# ButterWorth_8th_order_Filter.net
KiCad netlist of a schematic drawn in Altium Designer
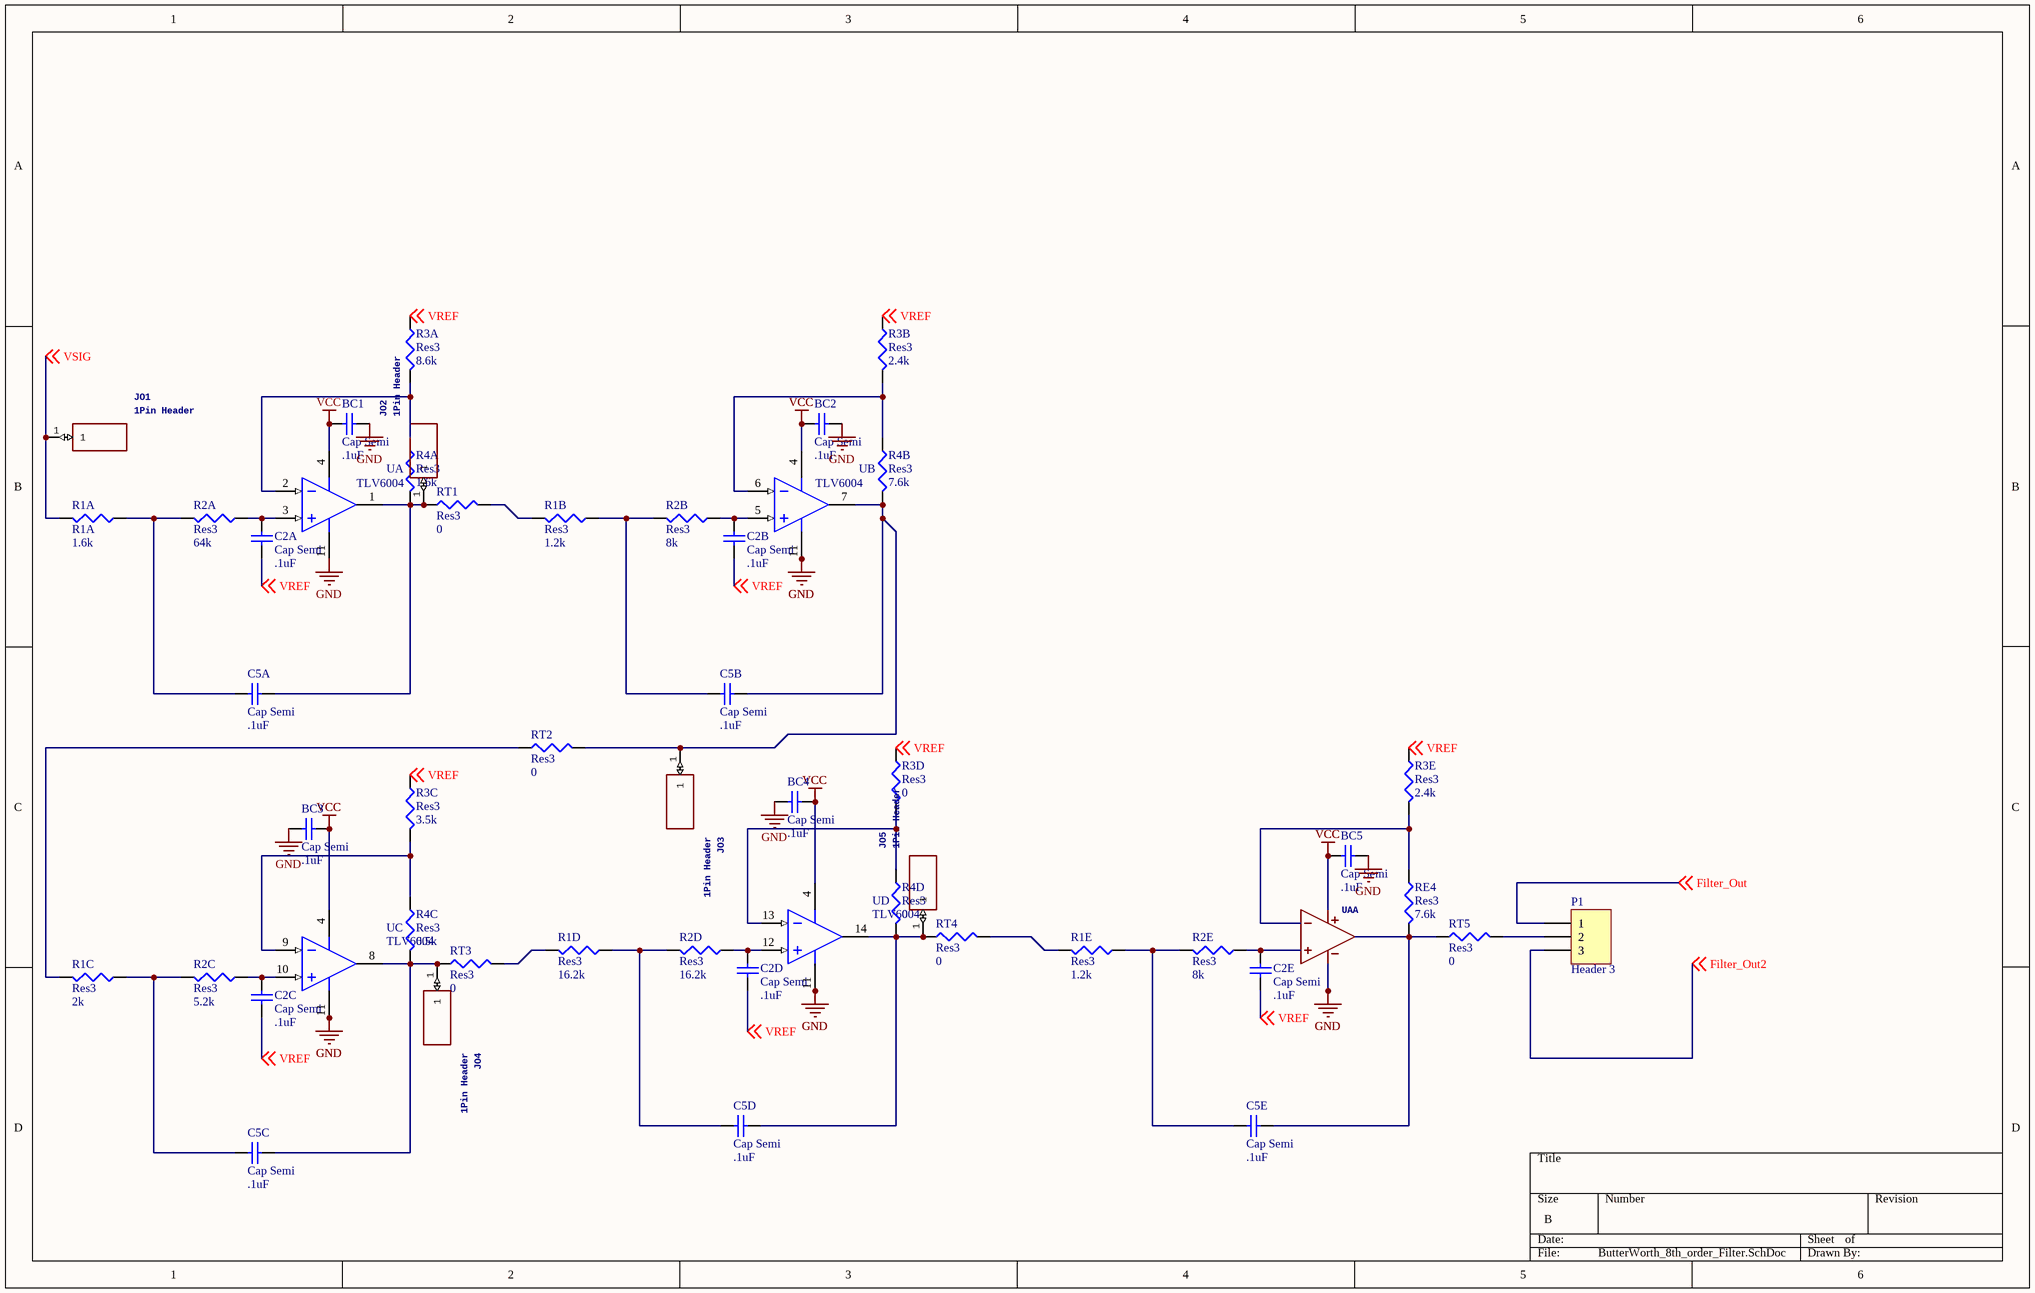
[diagram p0: ButterWorth_8th_order_Filter.SchDoc]

(export (version "E")
  (design (tool "Eeschema 10.0.6"))
  (components
    (comp (ref "BC1")
      (value "Cap Semi")
      (footprint "1608[0603]")
      (description "Capacitor (Semiconductor SIM Model)")
      (fields (field (name "ALTIUM_VALUE") ".1uF") (field (name "PUBLISHER") "Altium Limited"))
      (libsource (lib "Miscellaneous Devices") (part "Cap Semi"))
    )
    (comp (ref "BC2")
      (value "Cap Semi")
      (footprint "1608[0603]")
      (description "Capacitor (Semiconductor SIM Model)")
      (fields (field (name "ALTIUM_VALUE") ".1uF") (field (name "PUBLISHER") "Altium Limited"))
      (libsource (lib "Miscellaneous Devices") (part "Cap Semi"))
    )
    (comp (ref "BC3")
      (value "Cap Semi")
      (footprint "1608[0603]")
      (description "Capacitor (Semiconductor SIM Model)")
      (fields (field (name "ALTIUM_VALUE") ".1uF") (field (name "PUBLISHER") "Altium Limited"))
      (libsource (lib "Miscellaneous Devices") (part "Cap Semi"))
    )
    (comp (ref "BC4")
      (value "Cap Semi")
      (footprint "1608[0603]")
      (description "Capacitor (Semiconductor SIM Model)")
      (fields (field (name "ALTIUM_VALUE") ".1uF") (field (name "PUBLISHER") "Altium Limited"))
      (libsource (lib "Miscellaneous Devices") (part "Cap Semi"))
    )
    (comp (ref "BC5")
      (value "Cap Semi")
      (footprint "1608[0603]")
      (description "Capacitor (Semiconductor SIM Model)")
      (fields (field (name "ALTIUM_VALUE") ".1uF") (field (name "PUBLISHER") "Altium Limited"))
      (libsource (lib "Miscellaneous Devices") (part "Cap Semi"))
    )
    (comp (ref "C2A")
      (value "Cap Semi")
      (footprint "1608[0603]")
      (description "Capacitor (Semiconductor SIM Model)")
      (fields (field (name "ALTIUM_VALUE") ".1uF") (field (name "PUBLISHER") "Altium Limited"))
      (libsource (lib "Miscellaneous Devices") (part "Cap Semi"))
    )
    (comp (ref "C2B")
      (value "Cap Semi")
      (footprint "1608[0603]")
      (description "Capacitor (Semiconductor SIM Model)")
      (fields (field (name "ALTIUM_VALUE") ".1uF") (field (name "PUBLISHER") "Altium Limited"))
      (libsource (lib "Miscellaneous Devices") (part "Cap Semi"))
    )
    (comp (ref "C2C")
      (value "Cap Semi")
      (footprint "1608[0603]")
      (description "Capacitor (Semiconductor SIM Model)")
      (fields (field (name "ALTIUM_VALUE") ".1uF") (field (name "PUBLISHER") "Altium Limited"))
      (libsource (lib "Miscellaneous Devices") (part "Cap Semi"))
    )
    (comp (ref "C2D")
      (value "Cap Semi")
      (footprint "1608[0603]")
      (description "Capacitor (Semiconductor SIM Model)")
      (fields (field (name "ALTIUM_VALUE") ".1uF") (field (name "PUBLISHER") "Altium Limited"))
      (libsource (lib "Miscellaneous Devices") (part "Cap Semi"))
    )
    (comp (ref "C2E")
      (value "Cap Semi")
      (footprint "1608[0603]")
      (description "Capacitor (Semiconductor SIM Model)")
      (fields (field (name "ALTIUM_VALUE") ".1uF") (field (name "PUBLISHER") "Altium Limited"))
      (libsource (lib "Miscellaneous Devices") (part "Cap Semi"))
    )
    (comp (ref "C5A")
      (value "Cap Semi")
      (footprint "C1206")
      (description "Capacitor (Semiconductor SIM Model)")
      (fields (field (name "ALTIUM_VALUE") ".1uF") (field (name "PUBLISHER") "Altium Limited"))
      (libsource (lib "Miscellaneous Devices") (part "Cap Semi"))
    )
    (comp (ref "C5B")
      (value "Cap Semi")
      (footprint "C1206")
      (description "Capacitor (Semiconductor SIM Model)")
      (fields (field (name "ALTIUM_VALUE") ".1uF") (field (name "PUBLISHER") "Altium Limited"))
      (libsource (lib "Miscellaneous Devices") (part "Cap Semi"))
    )
    (comp (ref "C5C")
      (value "Cap Semi")
      (footprint "C1206")
      (description "Capacitor (Semiconductor SIM Model)")
      (fields (field (name "ALTIUM_VALUE") ".1uF") (field (name "PUBLISHER") "Altium Limited"))
      (libsource (lib "Miscellaneous Devices") (part "Cap Semi"))
    )
    (comp (ref "C5D")
      (value "Cap Semi")
      (footprint "C1206")
      (description "Capacitor (Semiconductor SIM Model)")
      (fields (field (name "ALTIUM_VALUE") ".1uF") (field (name "PUBLISHER") "Altium Limited"))
      (libsource (lib "Miscellaneous Devices") (part "Cap Semi"))
    )
    (comp (ref "C5E")
      (value "Cap Semi")
      (footprint "C1206")
      (description "Capacitor (Semiconductor SIM Model)")
      (fields (field (name "ALTIUM_VALUE") ".1uF") (field (name "PUBLISHER") "Altium Limited"))
      (libsource (lib "Miscellaneous Devices") (part "Cap Semi"))
    )
    (comp (ref "JO1")
      (value "1Pin Header")
      (footprint "68000-401HLF")
      (fields
        (field (name "MANUFACTURER_PART_NUMBER") "68000-401HLF")
        (field (name "RS_PART_NUMBER") "8632706")
      )
      (libsource (lib "68000-401HLF") (part "68000-401HLF"))
    )
    (comp (ref "JO2")
      (value "1Pin Header")
      (footprint "68000-401HLF")
      (fields
        (field (name "MANUFACTURER_PART_NUMBER") "68000-401HLF")
        (field (name "RS_PART_NUMBER") "8632706")
      )
      (libsource (lib "68000-401HLF") (part "68000-401HLF"))
    )
    (comp (ref "JO3")
      (value "1Pin Header")
      (footprint "68000-401HLF")
      (fields
        (field (name "MANUFACTURER_PART_NUMBER") "68000-401HLF")
        (field (name "RS_PART_NUMBER") "8632706")
      )
      (libsource (lib "68000-401HLF") (part "68000-401HLF"))
    )
    (comp (ref "JO4")
      (value "1Pin Header")
      (footprint "68000-401HLF")
      (fields
        (field (name "MANUFACTURER_PART_NUMBER") "68000-401HLF")
        (field (name "RS_PART_NUMBER") "8632706")
      )
      (libsource (lib "68000-401HLF") (part "68000-401HLF"))
    )
    (comp (ref "JO5")
      (value "1Pin Header")
      (footprint "68000-401HLF")
      (fields
        (field (name "MANUFACTURER_PART_NUMBER") "68000-401HLF")
        (field (name "RS_PART_NUMBER") "8632706")
      )
      (libsource (lib "68000-401HLF") (part "68000-401HLF"))
    )
    (comp (ref "P1")
      (value "Header 3")
      (footprint "HDRV3W95P0X254_1X3_762X254X869")
      (description "Header, 3-Pin")
      (fields (field (name "PUBLISHER") "Altium Limited"))
      (libsource (lib "Miscellaneous Connectors") (part "Header 3"))
    )
    (comp (ref "R1A")
      (value "R1A")
      (footprint "1608[0603]")
      (description "Resistor")
      (fields (field (name "ALTIUM_VALUE") "1.6k") (field (name "PUBLISHER") "Altium Limited"))
      (libsource (lib "Miscellaneous Devices") (part "Res3"))
    )
    (comp (ref "R1B")
      (value "Res3")
      (footprint "1608[0603]")
      (description "Resistor")
      (fields (field (name "ALTIUM_VALUE") "1.2k") (field (name "PUBLISHER") "Altium Limited"))
      (libsource (lib "Miscellaneous Devices") (part "Res3"))
    )
    (comp (ref "R1C")
      (value "Res3")
      (footprint "1608[0603]")
      (description "Resistor")
      (fields (field (name "ALTIUM_VALUE") "2k") (field (name "PUBLISHER") "Altium Limited"))
      (libsource (lib "Miscellaneous Devices") (part "Res3"))
    )
    (comp (ref "R1D")
      (value "Res3")
      (footprint "1608[0603]")
      (description "Resistor")
      (fields (field (name "ALTIUM_VALUE") "16.2k") (field (name "PUBLISHER") "Altium Limited"))
      (libsource (lib "Miscellaneous Devices") (part "Res3"))
    )
    (comp (ref "R1E")
      (value "Res3")
      (footprint "1608[0603]")
      (description "Resistor")
      (fields (field (name "ALTIUM_VALUE") "1.2k") (field (name "PUBLISHER") "Altium Limited"))
      (libsource (lib "Miscellaneous Devices") (part "Res3"))
    )
    (comp (ref "R2A")
      (value "Res3")
      (footprint "1608[0603]")
      (description "Resistor")
      (fields (field (name "ALTIUM_VALUE") "64k") (field (name "PUBLISHER") "Altium Limited"))
      (libsource (lib "Miscellaneous Devices") (part "Res3"))
    )
    (comp (ref "R2B")
      (value "Res3")
      (footprint "1608[0603]")
      (description "Resistor")
      (fields (field (name "ALTIUM_VALUE") "8k") (field (name "PUBLISHER") "Altium Limited"))
      (libsource (lib "Miscellaneous Devices") (part "Res3"))
    )
    (comp (ref "R2C")
      (value "Res3")
      (footprint "1608[0603]")
      (description "Resistor")
      (fields (field (name "ALTIUM_VALUE") "5.2k") (field (name "PUBLISHER") "Altium Limited"))
      (libsource (lib "Miscellaneous Devices") (part "Res3"))
    )
    (comp (ref "R2D")
      (value "Res3")
      (footprint "1608[0603]")
      (description "Resistor")
      (fields (field (name "ALTIUM_VALUE") "16.2k") (field (name "PUBLISHER") "Altium Limited"))
      (libsource (lib "Miscellaneous Devices") (part "Res3"))
    )
    (comp (ref "R2E")
      (value "Res3")
      (footprint "1608[0603]")
      (description "Resistor")
      (fields (field (name "ALTIUM_VALUE") "8k") (field (name "PUBLISHER") "Altium Limited"))
      (libsource (lib "Miscellaneous Devices") (part "Res3"))
    )
    (comp (ref "R3A")
      (value "Res3")
      (footprint "1608[0603]")
      (description "Resistor")
      (fields (field (name "ALTIUM_VALUE") "8.6k") (field (name "PUBLISHER") "Altium Limited"))
      (libsource (lib "Miscellaneous Devices") (part "Res3"))
    )
    (comp (ref "R3B")
      (value "Res3")
      (footprint "1608[0603]")
      (description "Resistor")
      (fields (field (name "ALTIUM_VALUE") "2.4k") (field (name "PUBLISHER") "Altium Limited"))
      (libsource (lib "Miscellaneous Devices") (part "Res3"))
    )
    (comp (ref "R3C")
      (value "Res3")
      (footprint "1608[0603]")
      (description "Resistor")
      (fields (field (name "ALTIUM_VALUE") "3.5k") (field (name "PUBLISHER") "Altium Limited"))
      (libsource (lib "Miscellaneous Devices") (part "Res3"))
    )
    (comp (ref "R3D")
      (value "Res3")
      (footprint "1608[0603]")
      (description "Resistor")
      (fields (field (name "ALTIUM_VALUE") "0") (field (name "PUBLISHER") "Altium Limited"))
      (libsource (lib "Miscellaneous Devices") (part "Res3"))
    )
    (comp (ref "R3E")
      (value "Res3")
      (footprint "1608[0603]")
      (description "Resistor")
      (fields (field (name "ALTIUM_VALUE") "2.4k") (field (name "PUBLISHER") "Altium Limited"))
      (libsource (lib "Miscellaneous Devices") (part "Res3"))
    )
    (comp (ref "R4A")
      (value "Res3")
      (footprint "1608[0603]")
      (description "Resistor")
      (fields (field (name "ALTIUM_VALUE") "1.6k") (field (name "PUBLISHER") "Altium Limited"))
      (libsource (lib "Miscellaneous Devices") (part "Res3"))
    )
    (comp (ref "R4B")
      (value "Res3")
      (footprint "1608[0603]")
      (description "Resistor")
      (fields (field (name "ALTIUM_VALUE") "7.6k") (field (name "PUBLISHER") "Altium Limited"))
      (libsource (lib "Miscellaneous Devices") (part "Res3"))
    )
    (comp (ref "R4C")
      (value "Res3")
      (footprint "1608[0603]")
      (description "Resistor")
      (fields (field (name "ALTIUM_VALUE") "6.5k") (field (name "PUBLISHER") "Altium Limited"))
      (libsource (lib "Miscellaneous Devices") (part "Res3"))
    )
    (comp (ref "R4D")
      (value "Res3")
      (footprint "1608[0603]")
      (description "Resistor")
      (fields (field (name "ALTIUM_VALUE") "0") (field (name "PUBLISHER") "Altium Limited"))
      (libsource (lib "Miscellaneous Devices") (part "Res3"))
    )
    (comp (ref "RE4")
      (value "Res3")
      (footprint "1608[0603]")
      (description "Resistor")
      (fields (field (name "ALTIUM_VALUE") "7.6k") (field (name "PUBLISHER") "Altium Limited"))
      (libsource (lib "Miscellaneous Devices") (part "Res3"))
    )
    (comp (ref "RT1")
      (value "Res3")
      (footprint "1608[0603]")
      (description "Resistor")
      (fields (field (name "ALTIUM_VALUE") "0") (field (name "PUBLISHER") "Altium Limited"))
      (libsource (lib "Miscellaneous Devices") (part "Res3"))
    )
    (comp (ref "RT2")
      (value "Res3")
      (footprint "1608[0603]")
      (description "Resistor")
      (fields (field (name "ALTIUM_VALUE") "0") (field (name "PUBLISHER") "Altium Limited"))
      (libsource (lib "Miscellaneous Devices") (part "Res3"))
    )
    (comp (ref "RT3")
      (value "Res3")
      (footprint "1608[0603]")
      (description "Resistor")
      (fields (field (name "ALTIUM_VALUE") "0") (field (name "PUBLISHER") "Altium Limited"))
      (libsource (lib "Miscellaneous Devices") (part "Res3"))
    )
    (comp (ref "RT4")
      (value "Res3")
      (footprint "1608[0603]")
      (description "Resistor")
      (fields (field (name "ALTIUM_VALUE") "0") (field (name "PUBLISHER") "Altium Limited"))
      (libsource (lib "Miscellaneous Devices") (part "Res3"))
    )
    (comp (ref "RT5")
      (value "Res3")
      (footprint "1608[0603]")
      (description "Resistor")
      (fields (field (name "ALTIUM_VALUE") "0") (field (name "PUBLISHER") "Altium Limited"))
      (libsource (lib "Miscellaneous Devices") (part "Res3"))
    )
    (comp (ref "U")
      (value "TLV6004")
      (footprint "SOP65P640X120-14N")
      (description "Low Power Quad Differential Comparator")
      (fields (field (name "PUBLISHER") "Altium Limited"))
      (libsource (lib "TI Analog Comparator") (part "LP2901D"))
    )
    (comp (ref "UAA")
      (value "Universal Opamp model that allows 4 different levels of simulation accuracy.  See ./examples/Educational/UniversalOpamp2.asc for details.  En and in are equivalent voltage and current noises.  Enk and ink are the respective corner frequencies.  Phimargin is used to set the 2nd pole or delay to the approximate phase margin for level.3a and level.3b.  This version uses the new, experimental level 2 switch as the output devices.")
      (footprint "SOT95P280X100-5N")
      (fields (field (name "LIBRARYNAME") "Opamps"))
      (libsource (lib "Opamps") (part "UNIVERSALOPAMP2"))
    )
  )
  (nets
    (net (code "1") (name "Filter_Out") (class "Default")
      (node (ref "P1") (pin "1") (pinfunction "1_1") (pintype "passive"))
    )
    (net (code "2") (name "Filter_Out2") (class "Default")
      (node (ref "P1") (pin "3") (pinfunction "3_3") (pintype "passive"))
    )
    (net (code "3") (name "GND") (class "Default")
      (node (ref "BC1") (pin "1") (pinfunction "1_1") (pintype "passive"))
      (node (ref "BC2") (pin "1") (pinfunction "1_1") (pintype "passive"))
      (node (ref "BC3") (pin "2") (pinfunction "2_2") (pintype "passive"))
      (node (ref "BC4") (pin "2") (pinfunction "2_2") (pintype "passive"))
      (node (ref "BC5") (pin "1") (pinfunction "1_1") (pintype "passive"))
      (node (ref "U") (pin "11") (pinfunction "V-_11") (pintype "power_in"))
      (node (ref "UAA") (pin "2") (pinfunction "V-_2") (pintype "power_in"))
    )
    (net (code "4") (name "Net-(C5A-Pad2)") (class "Default")
      (node (ref "C5A") (pin "2") (pinfunction "2_2") (pintype "passive"))
      (node (ref "R1A") (pin "2") (pinfunction "2_2") (pintype "passive"))
      (node (ref "R2A") (pin "1") (pinfunction "1_1") (pintype "passive"))
    )
    (net (code "5") (name "Net-(C5B-Pad2)") (class "Default")
      (node (ref "C5B") (pin "2") (pinfunction "2_2") (pintype "passive"))
      (node (ref "R1B") (pin "2") (pinfunction "2_2") (pintype "passive"))
      (node (ref "R2B") (pin "1") (pinfunction "1_1") (pintype "passive"))
    )
    (net (code "6") (name "Net-(C5C-Pad2)") (class "Default")
      (node (ref "C5C") (pin "2") (pinfunction "2_2") (pintype "passive"))
      (node (ref "R1C") (pin "2") (pinfunction "2_2") (pintype "passive"))
      (node (ref "R2C") (pin "1") (pinfunction "1_1") (pintype "passive"))
    )
    (net (code "7") (name "Net-(C5D-Pad2)") (class "Default")
      (node (ref "C5D") (pin "2") (pinfunction "2_2") (pintype "passive"))
      (node (ref "R1D") (pin "2") (pinfunction "2_2") (pintype "passive"))
      (node (ref "R2D") (pin "1") (pinfunction "1_1") (pintype "passive"))
    )
    (net (code "8") (name "Net-(C5E-Pad2)") (class "Default")
      (node (ref "C5E") (pin "2") (pinfunction "2_2") (pintype "passive"))
      (node (ref "R1E") (pin "2") (pinfunction "2_2") (pintype "passive"))
      (node (ref "R2E") (pin "1") (pinfunction "1_1") (pintype "passive"))
    )
    (net (code "9") (name "Net-(P1-Pad2)") (class "Default")
      (node (ref "P1") (pin "2") (pinfunction "2_2") (pintype "passive"))
      (node (ref "RT5") (pin "1") (pinfunction "1_1") (pintype "passive"))
    )
    (net (code "10") (name "Net-(R1B-Pad1)") (class "Default")
      (node (ref "R1B") (pin "1") (pinfunction "1_1") (pintype "passive"))
      (node (ref "RT1") (pin "1") (pinfunction "1_1") (pintype "passive"))
    )
    (net (code "11") (name "Net-(R1C-Pad1)") (class "Default")
      (node (ref "R1C") (pin "1") (pinfunction "1_1") (pintype "passive"))
      (node (ref "RT2") (pin "2") (pinfunction "2_2") (pintype "passive"))
    )
    (net (code "12") (name "Net-(R1D-Pad1)") (class "Default")
      (node (ref "R1D") (pin "1") (pinfunction "1_1") (pintype "passive"))
      (node (ref "RT3") (pin "1") (pinfunction "1_1") (pintype "passive"))
    )
    (net (code "13") (name "Net-(R1E-Pad1)") (class "Default")
      (node (ref "R1E") (pin "1") (pinfunction "1_1") (pintype "passive"))
      (node (ref "RT4") (pin "1") (pinfunction "1_1") (pintype "passive"))
    )
    (net (code "14") (name "Net-(UA-IN+)") (class "Default")
      (node (ref "C2A") (pin "2") (pinfunction "2_2") (pintype "passive"))
      (node (ref "R2A") (pin "2") (pinfunction "2_2") (pintype "passive"))
      (node (ref "U") (pin "3") (pinfunction "IN+_3") (pintype "input"))
    )
    (net (code "15") (name "Net-(UA-IN-)") (class "Default")
      (node (ref "R3A") (pin "1") (pinfunction "1_1") (pintype "passive"))
      (node (ref "R4A") (pin "2") (pinfunction "2_2") (pintype "passive"))
      (node (ref "U") (pin "2") (pinfunction "IN-_2") (pintype "input"))
    )
    (net (code "16") (name "Net-(UA-OUT)") (class "Default")
      (node (ref "C5A") (pin "1") (pinfunction "1_1") (pintype "passive"))
      (node (ref "JO2") (pin "1") (pinfunction "1_1") (pintype "bidirectional"))
      (node (ref "R4A") (pin "1") (pinfunction "1_1") (pintype "passive"))
      (node (ref "RT1") (pin "2") (pinfunction "2_2") (pintype "passive"))
      (node (ref "U") (pin "1") (pinfunction "OUT_1") (pintype "open_collector"))
    )
    (net (code "17") (name "Net-(UAA-IN+)") (class "Default")
      (node (ref "C2E") (pin "2") (pinfunction "2_2") (pintype "passive"))
      (node (ref "R2E") (pin "2") (pinfunction "2_2") (pintype "passive"))
      (node (ref "UAA") (pin "3") (pinfunction "IN+_3") (pintype "input"))
    )
    (net (code "18") (name "Net-(UAA-IN-)") (class "Default")
      (node (ref "R3E") (pin "1") (pinfunction "1_1") (pintype "passive"))
      (node (ref "RE4") (pin "2") (pinfunction "2_2") (pintype "passive"))
      (node (ref "UAA") (pin "4") (pinfunction "IN-_4") (pintype "input"))
    )
    (net (code "19") (name "Net-(UAA-OUT)") (class "Default")
      (node (ref "C5E") (pin "1") (pinfunction "1_1") (pintype "passive"))
      (node (ref "RE4") (pin "1") (pinfunction "1_1") (pintype "passive"))
      (node (ref "RT5") (pin "2") (pinfunction "2_2") (pintype "passive"))
      (node (ref "UAA") (pin "1") (pinfunction "OUT_1") (pintype "output"))
    )
    (net (code "20") (name "Net-(UB-IN+)") (class "Default")
      (node (ref "C2B") (pin "2") (pinfunction "2_2") (pintype "passive"))
      (node (ref "R2B") (pin "2") (pinfunction "2_2") (pintype "passive"))
      (node (ref "U") (pin "5") (pinfunction "IN+_5") (pintype "input"))
    )
    (net (code "21") (name "Net-(UB-IN-)") (class "Default")
      (node (ref "R3B") (pin "1") (pinfunction "1_1") (pintype "passive"))
      (node (ref "R4B") (pin "2") (pinfunction "2_2") (pintype "passive"))
      (node (ref "U") (pin "6") (pinfunction "IN-_6") (pintype "input"))
    )
    (net (code "22") (name "Net-(UB-OUT)") (class "Default")
      (node (ref "C5B") (pin "1") (pinfunction "1_1") (pintype "passive"))
      (node (ref "JO3") (pin "1") (pinfunction "1_1") (pintype "bidirectional"))
      (node (ref "R4B") (pin "1") (pinfunction "1_1") (pintype "passive"))
      (node (ref "RT2") (pin "1") (pinfunction "1_1") (pintype "passive"))
      (node (ref "U") (pin "7") (pinfunction "OUT_7") (pintype "open_collector"))
    )
    (net (code "23") (name "Net-(UC-IN+)") (class "Default")
      (node (ref "C2C") (pin "2") (pinfunction "2_2") (pintype "passive"))
      (node (ref "R2C") (pin "2") (pinfunction "2_2") (pintype "passive"))
      (node (ref "U") (pin "10") (pinfunction "IN+_10") (pintype "input"))
    )
    (net (code "24") (name "Net-(UC-IN-)") (class "Default")
      (node (ref "R3C") (pin "1") (pinfunction "1_1") (pintype "passive"))
      (node (ref "R4C") (pin "2") (pinfunction "2_2") (pintype "passive"))
      (node (ref "U") (pin "9") (pinfunction "IN-_9") (pintype "input"))
    )
    (net (code "25") (name "Net-(UC-OUT)") (class "Default")
      (node (ref "C5C") (pin "1") (pinfunction "1_1") (pintype "passive"))
      (node (ref "JO4") (pin "1") (pinfunction "1_1") (pintype "bidirectional"))
      (node (ref "R4C") (pin "1") (pinfunction "1_1") (pintype "passive"))
      (node (ref "RT3") (pin "2") (pinfunction "2_2") (pintype "passive"))
      (node (ref "U") (pin "8") (pinfunction "OUT_8") (pintype "open_collector"))
    )
    (net (code "26") (name "Net-(UD-IN+)") (class "Default")
      (node (ref "C2D") (pin "2") (pinfunction "2_2") (pintype "passive"))
      (node (ref "R2D") (pin "2") (pinfunction "2_2") (pintype "passive"))
      (node (ref "U") (pin "12") (pinfunction "IN+_12") (pintype "input"))
    )
    (net (code "27") (name "Net-(UD-IN-)") (class "Default")
      (node (ref "R3D") (pin "1") (pinfunction "1_1") (pintype "passive"))
      (node (ref "R4D") (pin "2") (pinfunction "2_2") (pintype "passive"))
      (node (ref "U") (pin "13") (pinfunction "IN-_13") (pintype "input"))
    )
    (net (code "28") (name "Net-(UD-OUT)") (class "Default")
      (node (ref "C5D") (pin "1") (pinfunction "1_1") (pintype "passive"))
      (node (ref "JO5") (pin "1") (pinfunction "1_1") (pintype "bidirectional"))
      (node (ref "R4D") (pin "1") (pinfunction "1_1") (pintype "passive"))
      (node (ref "RT4") (pin "2") (pinfunction "2_2") (pintype "passive"))
      (node (ref "U") (pin "14") (pinfunction "OUT_14") (pintype "open_collector"))
    )
    (net (code "29") (name "VCC") (class "Default")
      (node (ref "BC1") (pin "2") (pinfunction "2_2") (pintype "passive"))
      (node (ref "BC2") (pin "2") (pinfunction "2_2") (pintype "passive"))
      (node (ref "BC3") (pin "1") (pinfunction "1_1") (pintype "passive"))
      (node (ref "BC4") (pin "1") (pinfunction "1_1") (pintype "passive"))
      (node (ref "BC5") (pin "2") (pinfunction "2_2") (pintype "passive"))
      (node (ref "U") (pin "4") (pinfunction "V+_4") (pintype "power_in"))
      (node (ref "UAA") (pin "5") (pinfunction "V+_5") (pintype "power_in"))
    )
    (net (code "30") (name "VREF") (class "Default")
      (node (ref "C2A") (pin "1") (pinfunction "1_1") (pintype "passive"))
      (node (ref "C2B") (pin "1") (pinfunction "1_1") (pintype "passive"))
      (node (ref "C2C") (pin "1") (pinfunction "1_1") (pintype "passive"))
      (node (ref "C2D") (pin "1") (pinfunction "1_1") (pintype "passive"))
      (node (ref "C2E") (pin "1") (pinfunction "1_1") (pintype "passive"))
      (node (ref "R3A") (pin "2") (pinfunction "2_2") (pintype "passive"))
      (node (ref "R3B") (pin "2") (pinfunction "2_2") (pintype "passive"))
      (node (ref "R3C") (pin "2") (pinfunction "2_2") (pintype "passive"))
      (node (ref "R3D") (pin "2") (pinfunction "2_2") (pintype "passive"))
      (node (ref "R3E") (pin "2") (pinfunction "2_2") (pintype "passive"))
    )
    (net (code "31") (name "VSIG") (class "Default")
      (node (ref "JO1") (pin "1") (pinfunction "1_1") (pintype "bidirectional"))
      (node (ref "R1A") (pin "1") (pinfunction "1_1") (pintype "passive"))
    )
  )
)
